# 03_H7_PWR.net
KiCad netlist of a schematic drawn in Altium Designer
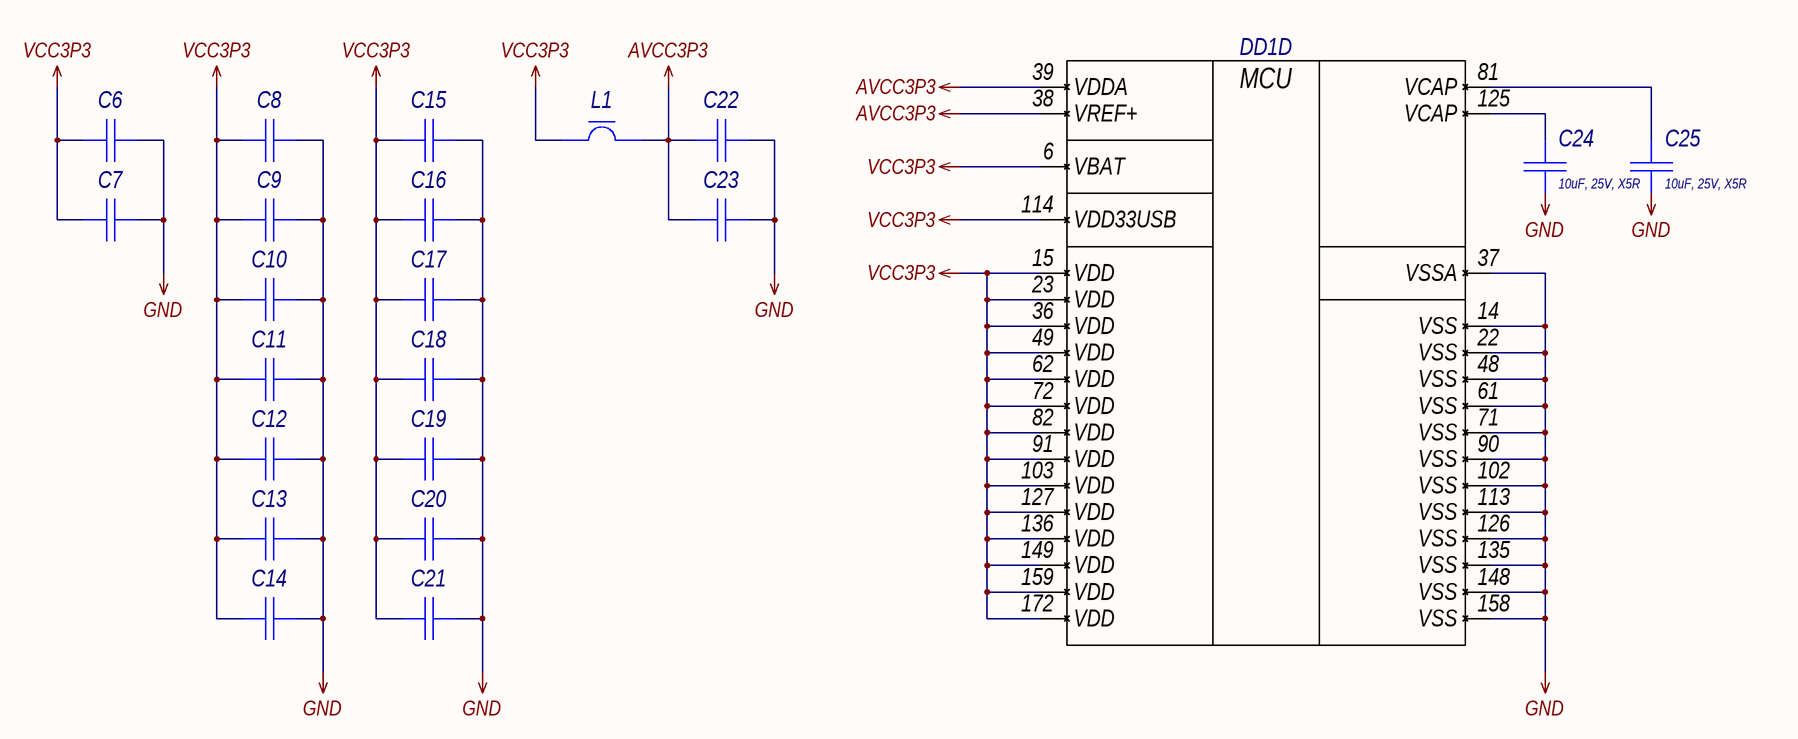
[diagram p0: 03_H7_PWR.SchDoc]

(export (version "E")
  (design (tool "Eeschema 10.0.6"))
  (components
    (comp (ref "C6")
      (value "Capacitor")
      (footprint "C0402_L")
      (fields
        (field (name "PART NUMBER") "GRM155R61A475MEAAD")
        (field (name "VOLTAGE") "10V")
        (field (name "TOLERANCE") "±20%")
        (field (name "PUBLISHER") "Andrew Danich")
      )
      (libsource (lib "ADLib") (part "Capacitor"))
    )
    (comp (ref "C7")
      (value "Capacitor")
      (footprint "C0402_L")
      (fields
        (field (name "PART NUMBER") "GRM155R61A475MEAAD")
        (field (name "VOLTAGE") "10V")
        (field (name "TOLERANCE") "±20%")
        (field (name "PUBLISHER") "Andrew Danich")
      )
      (libsource (lib "ADLib") (part "Capacitor"))
    )
    (comp (ref "C8")
      (value "Capacitor")
      (footprint "C0402_L")
      (fields
        (field (name "PART NUMBER") "GCM155R71C104KA55D")
        (field (name "VOLTAGE") "16V")
        (field (name "TOLERANCE") "±10%")
        (field (name "PUBLISHER") "Andrew Danich")
      )
      (libsource (lib "ADLib") (part "Capacitor"))
    )
    (comp (ref "C9")
      (value "Capacitor")
      (footprint "C0402_L")
      (fields
        (field (name "PART NUMBER") "GCM155R71C104KA55D")
        (field (name "VOLTAGE") "16V")
        (field (name "TOLERANCE") "±10%")
        (field (name "PUBLISHER") "Andrew Danich")
      )
      (libsource (lib "ADLib") (part "Capacitor"))
    )
    (comp (ref "C10")
      (value "Capacitor")
      (footprint "C0402_L")
      (fields
        (field (name "PART NUMBER") "GCM155R71C104KA55D")
        (field (name "VOLTAGE") "16V")
        (field (name "TOLERANCE") "±10%")
        (field (name "PUBLISHER") "Andrew Danich")
      )
      (libsource (lib "ADLib") (part "Capacitor"))
    )
    (comp (ref "C11")
      (value "Capacitor")
      (footprint "C0402_L")
      (fields
        (field (name "PART NUMBER") "GCM155R71C104KA55D")
        (field (name "VOLTAGE") "16V")
        (field (name "TOLERANCE") "±10%")
        (field (name "PUBLISHER") "Andrew Danich")
      )
      (libsource (lib "ADLib") (part "Capacitor"))
    )
    (comp (ref "C12")
      (value "Capacitor")
      (footprint "C0402_L")
      (fields
        (field (name "PART NUMBER") "GCM155R71C104KA55D")
        (field (name "VOLTAGE") "16V")
        (field (name "TOLERANCE") "±10%")
        (field (name "PUBLISHER") "Andrew Danich")
      )
      (libsource (lib "ADLib") (part "Capacitor"))
    )
    (comp (ref "C13")
      (value "Capacitor")
      (footprint "C0402_L")
      (fields
        (field (name "PART NUMBER") "GCM155R71C104KA55D")
        (field (name "VOLTAGE") "16V")
        (field (name "TOLERANCE") "±10%")
        (field (name "PUBLISHER") "Andrew Danich")
      )
      (libsource (lib "ADLib") (part "Capacitor"))
    )
    (comp (ref "C14")
      (value "Capacitor")
      (footprint "C0402_L")
      (fields
        (field (name "PART NUMBER") "GCM155R71C104KA55D")
        (field (name "VOLTAGE") "16V")
        (field (name "TOLERANCE") "±10%")
        (field (name "PUBLISHER") "Andrew Danich")
      )
      (libsource (lib "ADLib") (part "Capacitor"))
    )
    (comp (ref "C15")
      (value "Capacitor")
      (footprint "C0402_L")
      (fields
        (field (name "PART NUMBER") "GCM155R71C104KA55D")
        (field (name "VOLTAGE") "16V")
        (field (name "TOLERANCE") "±10%")
        (field (name "PUBLISHER") "Andrew Danich")
      )
      (libsource (lib "ADLib") (part "Capacitor"))
    )
    (comp (ref "C16")
      (value "Capacitor")
      (footprint "C0402_L")
      (fields
        (field (name "PART NUMBER") "GCM155R71C104KA55D")
        (field (name "VOLTAGE") "16V")
        (field (name "TOLERANCE") "±10%")
        (field (name "PUBLISHER") "Andrew Danich")
      )
      (libsource (lib "ADLib") (part "Capacitor"))
    )
    (comp (ref "C17")
      (value "Capacitor")
      (footprint "C0402_L")
      (fields
        (field (name "PART NUMBER") "GCM155R71C104KA55D")
        (field (name "VOLTAGE") "16V")
        (field (name "TOLERANCE") "±10%")
        (field (name "PUBLISHER") "Andrew Danich")
      )
      (libsource (lib "ADLib") (part "Capacitor"))
    )
    (comp (ref "C18")
      (value "Capacitor")
      (footprint "C0402_L")
      (fields
        (field (name "PART NUMBER") "GCM155R71C104KA55D")
        (field (name "VOLTAGE") "16V")
        (field (name "TOLERANCE") "±10%")
        (field (name "PUBLISHER") "Andrew Danich")
      )
      (libsource (lib "ADLib") (part "Capacitor"))
    )
    (comp (ref "C19")
      (value "Capacitor")
      (footprint "C0402_L")
      (fields
        (field (name "PART NUMBER") "GCM155R71C104KA55D")
        (field (name "VOLTAGE") "16V")
        (field (name "TOLERANCE") "±10%")
        (field (name "PUBLISHER") "Andrew Danich")
      )
      (libsource (lib "ADLib") (part "Capacitor"))
    )
    (comp (ref "C20")
      (value "Capacitor")
      (footprint "C0402_L")
      (fields
        (field (name "PART NUMBER") "GCM155R71C104KA55D")
        (field (name "VOLTAGE") "16V")
        (field (name "TOLERANCE") "±10%")
        (field (name "PUBLISHER") "Andrew Danich")
      )
      (libsource (lib "ADLib") (part "Capacitor"))
    )
    (comp (ref "C21")
      (value "Capacitor")
      (footprint "C0402_L")
      (fields
        (field (name "PART NUMBER") "GCM155R71C104KA55D")
        (field (name "VOLTAGE") "16V")
        (field (name "TOLERANCE") "±10%")
        (field (name "PUBLISHER") "Andrew Danich")
      )
      (libsource (lib "ADLib") (part "Capacitor"))
    )
    (comp (ref "C22")
      (value "Capacitor")
      (footprint "C0402_L")
      (fields
        (field (name "PART NUMBER") "GRM155C71A105KE11D")
        (field (name "VOLTAGE") "10V")
        (field (name "TOLERANCE") "±10%")
        (field (name "PUBLISHER") "Andrew Danich")
      )
      (libsource (lib "ADLib") (part "Capacitor"))
    )
    (comp (ref "C23")
      (value "Capacitor")
      (footprint "C0402_L")
      (fields
        (field (name "PART NUMBER") "GCM155R71C104KA55D")
        (field (name "VOLTAGE") "16V")
        (field (name "TOLERANCE") "±10%")
        (field (name "PUBLISHER") "Andrew Danich")
      )
      (libsource (lib "ADLib") (part "Capacitor"))
    )
    (comp (ref "C24")
      (value "Capacitor")
      (footprint "C0805_L")
      (fields
        (field (name "SCHEMATIC VALUE") "10uF, 25V, X5R")
        (field (name "PART NUMBER") "GRM21BR61E106KA73L")
        (field (name "VOLTAGE") "25V")
        (field (name "TOLERANCE") "±10%")
        (field (name "PUBLISHER") "Andrew Danich")
      )
      (libsource (lib "ADLib") (part "Capacitor"))
    )
    (comp (ref "C25")
      (value "Capacitor")
      (footprint "C0805_L")
      (fields
        (field (name "SCHEMATIC VALUE") "10uF, 25V, X5R")
        (field (name "PART NUMBER") "GRM21BR61E106KA73L")
        (field (name "VOLTAGE") "25V")
        (field (name "TOLERANCE") "±10%")
        (field (name "PUBLISHER") "Andrew Danich")
      )
      (libsource (lib "ADLib") (part "Capacitor"))
    )
    (comp (ref "DD1")
      (value "STM32H743IxT6-Series")
      (footprint "LQFP-176_050P2400X2400X160_N")
      (fields
        (field (name "PART NUMBER") "STM32H743IIT6")
        (field (name "MANUFACTURER") "STMicroelectronics")
        (field (name "PUBLISHER") "Andrew Danich")
      )
      (libsource (lib "ADLib") (part "STM32H743IxT6-Series"))
    )
    (comp (ref "L1")
      (value "FerriteBead")
      (footprint "L0402_L")
      (fields
        (field (name "PART NUMBER") "BLM15HD601SH1D")
        (field (name "TOLERANCE") "±25%")
        (field (name "MANUFACTURER") "Murata")
        (field (name "PUBLISHER") "Andrew Danich")
      )
      (libsource (lib "ADLib") (part "FerriteBead"))
    )
  )
  (nets
    (net (code "1") (name "AVCC3P3") (class "Default")
      (node (ref "C22") (pin "1") (pinfunction "1_1") (pintype "passive"))
      (node (ref "C23") (pin "1") (pinfunction "1_1") (pintype "passive"))
      (node (ref "DD1") (pin "38") (pinfunction "VREF+_38") (pintype "passive"))
      (node (ref "DD1") (pin "39") (pinfunction "VDDA_39") (pintype "power_in"))
      (node (ref "L1") (pin "2") (pinfunction "2_2") (pintype "passive"))
    )
    (net (code "2") (name "GND") (class "Default")
      (node (ref "C10") (pin "2") (pinfunction "2_2") (pintype "passive"))
      (node (ref "C11") (pin "2") (pinfunction "2_2") (pintype "passive"))
      (node (ref "C12") (pin "2") (pinfunction "2_2") (pintype "passive"))
      (node (ref "C13") (pin "2") (pinfunction "2_2") (pintype "passive"))
      (node (ref "C14") (pin "2") (pinfunction "2_2") (pintype "passive"))
      (node (ref "C15") (pin "2") (pinfunction "2_2") (pintype "passive"))
      (node (ref "C16") (pin "2") (pinfunction "2_2") (pintype "passive"))
      (node (ref "C17") (pin "2") (pinfunction "2_2") (pintype "passive"))
      (node (ref "C18") (pin "2") (pinfunction "2_2") (pintype "passive"))
      (node (ref "C19") (pin "2") (pinfunction "2_2") (pintype "passive"))
      (node (ref "C20") (pin "2") (pinfunction "2_2") (pintype "passive"))
      (node (ref "C21") (pin "2") (pinfunction "2_2") (pintype "passive"))
      (node (ref "C22") (pin "2") (pinfunction "2_2") (pintype "passive"))
      (node (ref "C23") (pin "2") (pinfunction "2_2") (pintype "passive"))
      (node (ref "C24") (pin "1") (pinfunction "1_1") (pintype "passive"))
      (node (ref "C25") (pin "1") (pinfunction "1_1") (pintype "passive"))
      (node (ref "C6") (pin "2") (pinfunction "2_2") (pintype "passive"))
      (node (ref "C7") (pin "2") (pinfunction "2_2") (pintype "passive"))
      (node (ref "C8") (pin "2") (pinfunction "2_2") (pintype "passive"))
      (node (ref "C9") (pin "2") (pinfunction "2_2") (pintype "passive"))
      (node (ref "DD1") (pin "102") (pinfunction "VSS_102") (pintype "power_in"))
      (node (ref "DD1") (pin "113") (pinfunction "VSS_113") (pintype "power_in"))
      (node (ref "DD1") (pin "126") (pinfunction "VSS_126") (pintype "power_in"))
      (node (ref "DD1") (pin "135") (pinfunction "VSS_135") (pintype "power_in"))
      (node (ref "DD1") (pin "14") (pinfunction "VSS_14") (pintype "power_in"))
      (node (ref "DD1") (pin "148") (pinfunction "VSS_148") (pintype "power_in"))
      (node (ref "DD1") (pin "158") (pinfunction "VSS_158") (pintype "power_in"))
      (node (ref "DD1") (pin "22") (pinfunction "VSS_22") (pintype "power_in"))
      (node (ref "DD1") (pin "37") (pinfunction "VSSA_37") (pintype "power_in"))
      (node (ref "DD1") (pin "48") (pinfunction "VSS_48") (pintype "power_in"))
      (node (ref "DD1") (pin "61") (pinfunction "VSS_61") (pintype "power_in"))
      (node (ref "DD1") (pin "71") (pinfunction "VSS_71") (pintype "power_in"))
      (node (ref "DD1") (pin "90") (pinfunction "VSS_90") (pintype "power_in"))
    )
    (net (code "3") (name "Net-(C24-Pad2)") (class "Default")
      (node (ref "C24") (pin "2") (pinfunction "2_2") (pintype "passive"))
      (node (ref "DD1") (pin "125") (pinfunction "VCAP_125") (pintype "passive"))
    )
    (net (code "4") (name "Net-(C25-Pad2)") (class "Default")
      (node (ref "C25") (pin "2") (pinfunction "2_2") (pintype "passive"))
      (node (ref "DD1") (pin "81") (pinfunction "VCAP_81") (pintype "passive"))
    )
    (net (code "5") (name "VCC3P3") (class "Default")
      (node (ref "C10") (pin "1") (pinfunction "1_1") (pintype "passive"))
      (node (ref "C11") (pin "1") (pinfunction "1_1") (pintype "passive"))
      (node (ref "C12") (pin "1") (pinfunction "1_1") (pintype "passive"))
      (node (ref "C13") (pin "1") (pinfunction "1_1") (pintype "passive"))
      (node (ref "C14") (pin "1") (pinfunction "1_1") (pintype "passive"))
      (node (ref "C15") (pin "1") (pinfunction "1_1") (pintype "passive"))
      (node (ref "C16") (pin "1") (pinfunction "1_1") (pintype "passive"))
      (node (ref "C17") (pin "1") (pinfunction "1_1") (pintype "passive"))
      (node (ref "C18") (pin "1") (pinfunction "1_1") (pintype "passive"))
      (node (ref "C19") (pin "1") (pinfunction "1_1") (pintype "passive"))
      (node (ref "C20") (pin "1") (pinfunction "1_1") (pintype "passive"))
      (node (ref "C21") (pin "1") (pinfunction "1_1") (pintype "passive"))
      (node (ref "C6") (pin "1") (pinfunction "1_1") (pintype "passive"))
      (node (ref "C7") (pin "1") (pinfunction "1_1") (pintype "passive"))
      (node (ref "C8") (pin "1") (pinfunction "1_1") (pintype "passive"))
      (node (ref "C9") (pin "1") (pinfunction "1_1") (pintype "passive"))
      (node (ref "DD1") (pin "103") (pinfunction "VDD_103") (pintype "power_in"))
      (node (ref "DD1") (pin "114") (pinfunction "VDD33USB_114") (pintype "power_in"))
      (node (ref "DD1") (pin "127") (pinfunction "VDD_127") (pintype "power_in"))
      (node (ref "DD1") (pin "136") (pinfunction "VDD_136") (pintype "power_in"))
      (node (ref "DD1") (pin "149") (pinfunction "VDD_149") (pintype "power_in"))
      (node (ref "DD1") (pin "15") (pinfunction "VDD_15") (pintype "power_in"))
      (node (ref "DD1") (pin "159") (pinfunction "VDD_159") (pintype "power_in"))
      (node (ref "DD1") (pin "172") (pinfunction "VDD_172") (pintype "power_in"))
      (node (ref "DD1") (pin "23") (pinfunction "VDD_23") (pintype "power_in"))
      (node (ref "DD1") (pin "36") (pinfunction "VDD_36") (pintype "power_in"))
      (node (ref "DD1") (pin "49") (pinfunction "VDD_49") (pintype "power_in"))
      (node (ref "DD1") (pin "6") (pinfunction "VBAT_6") (pintype "power_in"))
      (node (ref "DD1") (pin "62") (pinfunction "VDD_62") (pintype "power_in"))
      (node (ref "DD1") (pin "72") (pinfunction "VDD_72") (pintype "power_in"))
      (node (ref "DD1") (pin "82") (pinfunction "VDD_82") (pintype "power_in"))
      (node (ref "DD1") (pin "91") (pinfunction "VDD_91") (pintype "power_in"))
      (node (ref "L1") (pin "1") (pinfunction "1_1") (pintype "passive"))
    )
  )
)
